# 2045.net
KiCad netlist of a schematic drawn in EAGLE
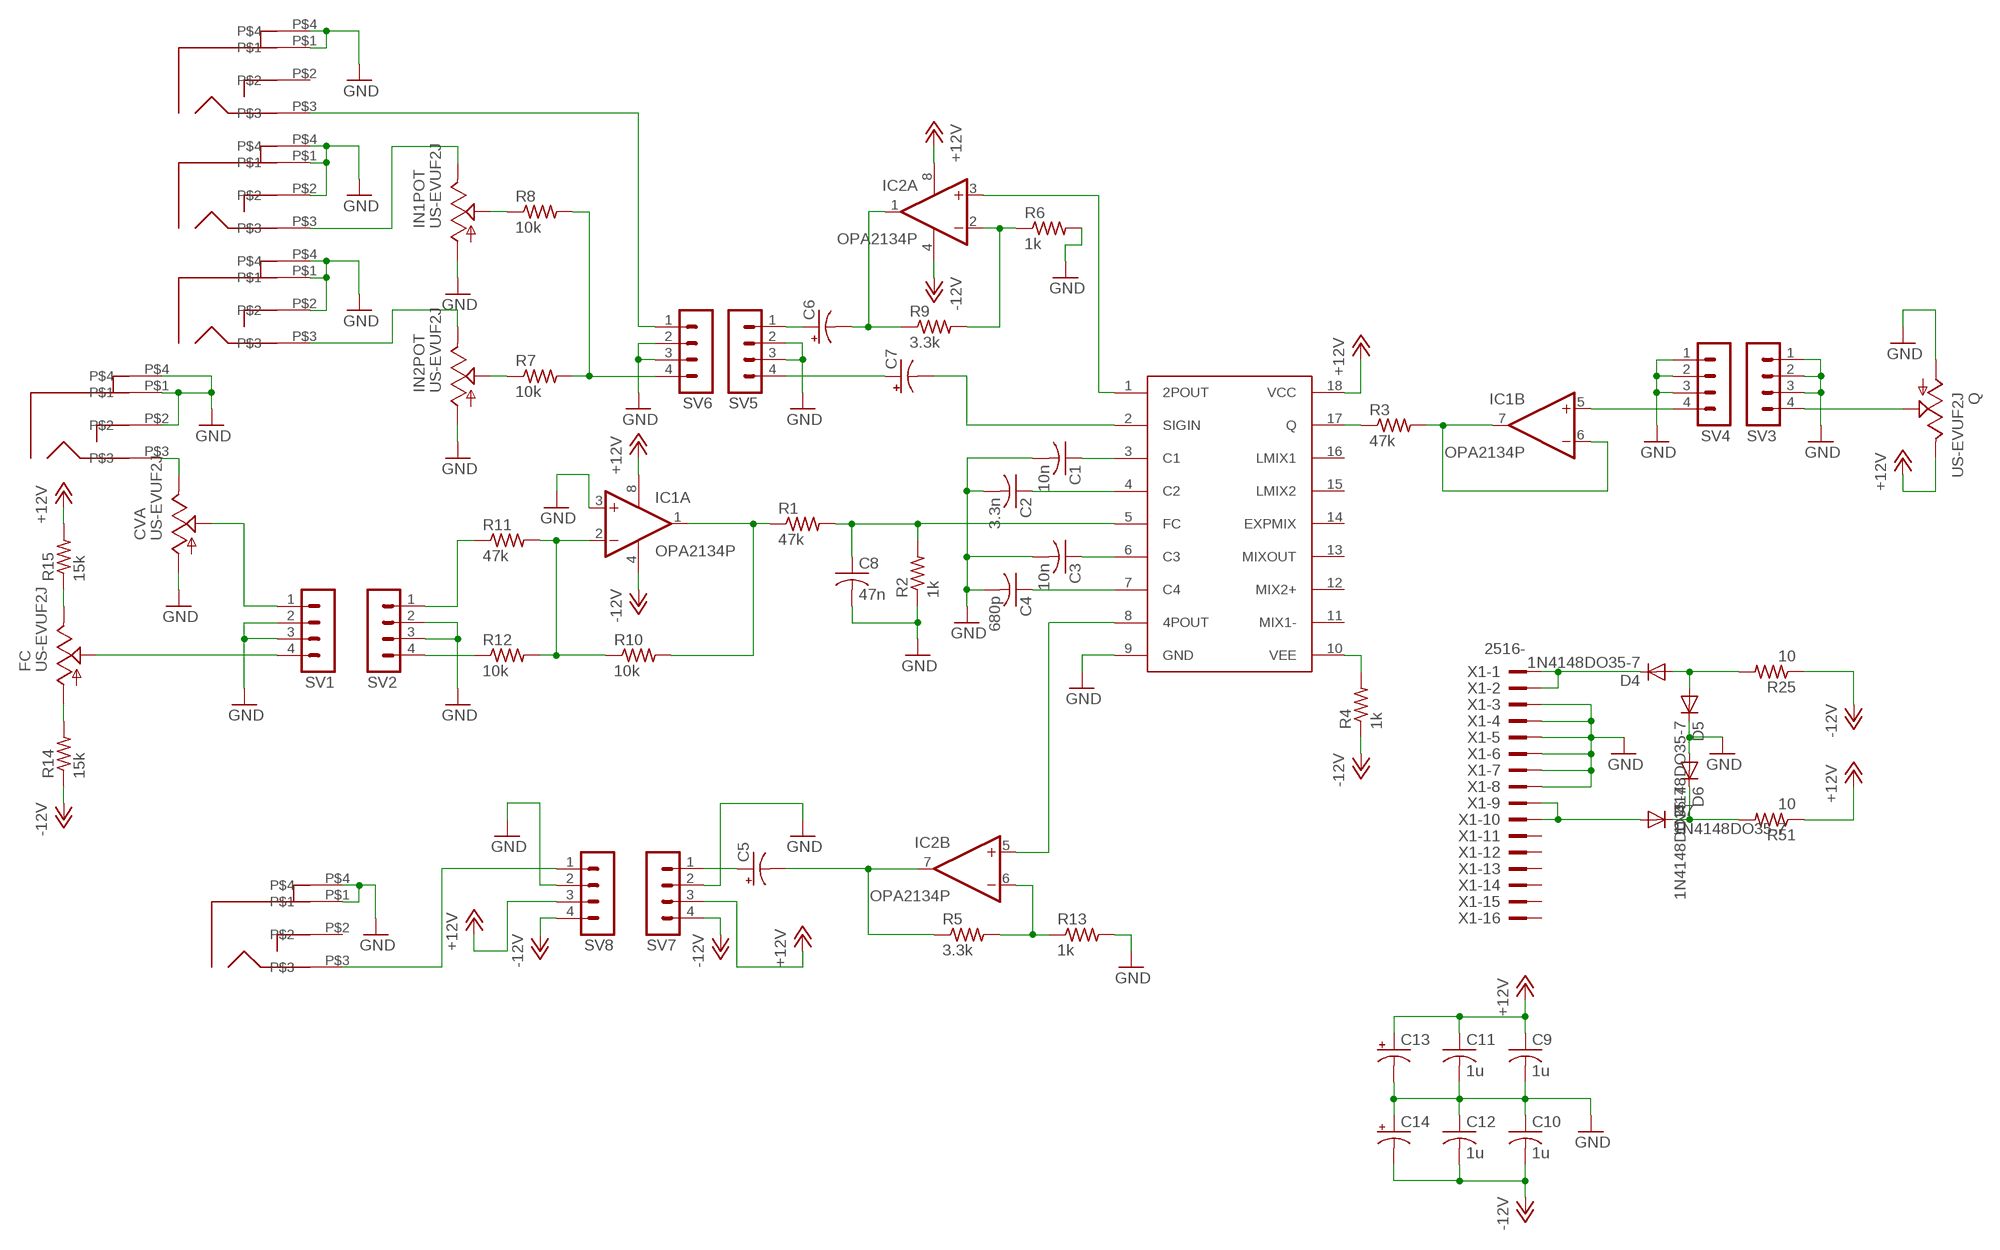
[diagram p0: schematic, sheet 1]

(export (version "E")
  (design (tool "Eeschema 10.0.6"))
  (components
    (comp (ref "2POUT")
      (value "PJ301BM")
      (footprint "eagle-import:PJ301BM")
      (libsource (lib "eagle-import") (part "PJ301BM"))
    )
    (comp (ref "4POUTPUT")
      (value "PJ301BM")
      (footprint "eagle-import:PJ301BM")
      (libsource (lib "eagle-import") (part "PJ301BM"))
    )
    (comp (ref "C1")
      (value "10n")
      (footprint "eagle-import:C050-025X075")
      (libsource (lib "eagle-import") (part "C-US050-025X075"))
    )
    (comp (ref "C2")
      (value "3.3n")
      (footprint "eagle-import:C050-025X075")
      (libsource (lib "eagle-import") (part "C-US050-025X075"))
    )
    (comp (ref "C3")
      (value "10n")
      (footprint "eagle-import:C050-025X075")
      (libsource (lib "eagle-import") (part "C-US050-025X075"))
    )
    (comp (ref "C4")
      (value "680p")
      (footprint "eagle-import:C050-025X075")
      (libsource (lib "eagle-import") (part "C-US050-025X075"))
    )
    (comp (ref "C5")
      (value "CPOL-USE2.5-7")
      (footprint "eagle-import:E2,5-7")
      (libsource (lib "eagle-import") (part "CPOL-USE2.5-7"))
    )
    (comp (ref "C6")
      (value "CPOL-USE2.5-7")
      (footprint "eagle-import:E2,5-7")
      (libsource (lib "eagle-import") (part "CPOL-USE2.5-7"))
    )
    (comp (ref "C7")
      (value "CPOL-USE2.5-7")
      (footprint "eagle-import:E2,5-7")
      (libsource (lib "eagle-import") (part "CPOL-USE2.5-7"))
    )
    (comp (ref "C8")
      (value "47n")
      (footprint "eagle-import:C050-025X075")
      (libsource (lib "eagle-import") (part "C-US050-025X075"))
    )
    (comp (ref "C9")
      (value "1u")
      (footprint "eagle-import:C050-025X075")
      (libsource (lib "eagle-import") (part "C-US050-025X075"))
    )
    (comp (ref "C10")
      (value "1u")
      (footprint "eagle-import:C050-025X075")
      (libsource (lib "eagle-import") (part "C-US050-025X075"))
    )
    (comp (ref "C11")
      (value "1u")
      (footprint "eagle-import:C050-025X075")
      (libsource (lib "eagle-import") (part "C-US050-025X075"))
    )
    (comp (ref "C12")
      (value "1u")
      (footprint "eagle-import:C050-025X075")
      (libsource (lib "eagle-import") (part "C-US050-025X075"))
    )
    (comp (ref "C13")
      (value "CPOL-USE2.5-7")
      (footprint "eagle-import:E2,5-7")
      (libsource (lib "eagle-import") (part "CPOL-USE2.5-7"))
    )
    (comp (ref "C14")
      (value "CPOL-USE2.5-7")
      (footprint "eagle-import:E2,5-7")
      (libsource (lib "eagle-import") (part "CPOL-USE2.5-7"))
    )
    (comp (ref "CVA")
      (value "US-EVUF2J")
      (footprint "eagle-import:EVUFXJ")
      (libsource (lib "eagle-import") (part "US-EVUF2J"))
    )
    (comp (ref "CVIN")
      (value "PJ301BM")
      (footprint "eagle-import:PJ301BM")
      (libsource (lib "eagle-import") (part "PJ301BM"))
    )
    (comp (ref "D4")
      (value "1N4148DO35-7")
      (footprint "eagle-import:DO35-7")
      (libsource (lib "eagle-import") (part "1N4148DO35-7"))
    )
    (comp (ref "D5")
      (value "1N4148DO35-7")
      (footprint "eagle-import:DO35-7")
      (libsource (lib "eagle-import") (part "1N4148DO35-7"))
    )
    (comp (ref "D6")
      (value "1N4148DO35-7")
      (footprint "eagle-import:DO35-7")
      (libsource (lib "eagle-import") (part "1N4148DO35-7"))
    )
    (comp (ref "D7")
      (value "1N4148DO35-7")
      (footprint "eagle-import:DO35-7")
      (libsource (lib "eagle-import") (part "1N4148DO35-7"))
    )
    (comp (ref "FC")
      (value "US-EVUF2J")
      (footprint "eagle-import:EVUFXJ")
      (libsource (lib "eagle-import") (part "US-EVUF2J"))
    )
    (comp (ref "IC1")
      (value "OPA2134P")
      (footprint "eagle-import:DIL08")
      (libsource (lib "eagle-import") (part "OPA2134P"))
    )
    (comp (ref "IC2")
      (value "OPA2134P")
      (footprint "eagle-import:DIL08")
      (libsource (lib "eagle-import") (part "OPA2134P"))
    )
    (comp (ref "IN")
      (value "PJ301BM")
      (footprint "eagle-import:PJ301BM")
      (libsource (lib "eagle-import") (part "PJ301BM"))
    )
    (comp (ref "IN1POT")
      (value "US-EVUF2J")
      (footprint "eagle-import:EVUFXJ")
      (libsource (lib "eagle-import") (part "US-EVUF2J"))
    )
    (comp (ref "IN2")
      (value "PJ301BM")
      (footprint "eagle-import:PJ301BM")
      (libsource (lib "eagle-import") (part "PJ301BM"))
    )
    (comp (ref "IN2POT")
      (value "US-EVUF2J")
      (footprint "eagle-import:EVUFXJ")
      (libsource (lib "eagle-import") (part "US-EVUF2J"))
    )
    (comp (ref "Q")
      (value "US-EVUF2J")
      (footprint "eagle-import:EVUFXJ")
      (libsource (lib "eagle-import") (part "US-EVUF2J"))
    )
    (comp (ref "R1")
      (value "47k")
      (footprint "eagle-import:0204_7")
      (libsource (lib "eagle-import") (part "R-US_0204/7"))
    )
    (comp (ref "R2")
      (value "1k")
      (footprint "eagle-import:0204_7")
      (libsource (lib "eagle-import") (part "R-US_0204/7"))
    )
    (comp (ref "R3")
      (value "47k")
      (footprint "eagle-import:0204_7")
      (libsource (lib "eagle-import") (part "R-US_0204/7"))
    )
    (comp (ref "R4")
      (value "1k")
      (footprint "eagle-import:0204_7")
      (libsource (lib "eagle-import") (part "R-US_0204/7"))
    )
    (comp (ref "R5")
      (value "3.3k")
      (footprint "eagle-import:0204_7")
      (libsource (lib "eagle-import") (part "R-US_0204/7"))
    )
    (comp (ref "R6")
      (value "1k")
      (footprint "eagle-import:0204_7")
      (libsource (lib "eagle-import") (part "R-US_0204/7"))
    )
    (comp (ref "R7")
      (value "10k")
      (footprint "eagle-import:0204_7")
      (libsource (lib "eagle-import") (part "R-US_0204/7"))
    )
    (comp (ref "R8")
      (value "10k")
      (footprint "eagle-import:0204_7")
      (libsource (lib "eagle-import") (part "R-US_0204/7"))
    )
    (comp (ref "R9")
      (value "3.3k")
      (footprint "eagle-import:0204_7")
      (libsource (lib "eagle-import") (part "R-US_0204/7"))
    )
    (comp (ref "R10")
      (value "10k")
      (footprint "eagle-import:0204_7")
      (libsource (lib "eagle-import") (part "R-US_0204/7"))
    )
    (comp (ref "R11")
      (value "47k")
      (footprint "eagle-import:0204_7")
      (libsource (lib "eagle-import") (part "R-US_0204/7"))
    )
    (comp (ref "R12")
      (value "10k")
      (footprint "eagle-import:0204_7")
      (libsource (lib "eagle-import") (part "R-US_0204/7"))
    )
    (comp (ref "R13")
      (value "1k")
      (footprint "eagle-import:0204_7")
      (libsource (lib "eagle-import") (part "R-US_0204/7"))
    )
    (comp (ref "R14")
      (value "15k")
      (footprint "eagle-import:0204_7")
      (libsource (lib "eagle-import") (part "R-US_0204/7"))
    )
    (comp (ref "R15")
      (value "15k")
      (footprint "eagle-import:0204_7")
      (libsource (lib "eagle-import") (part "R-US_0204/7"))
    )
    (comp (ref "R25")
      (value "10")
      (footprint "eagle-import:0207_2V")
      (libsource (lib "eagle-import") (part "R-US_0207/2V"))
    )
    (comp (ref "R51")
      (value "10")
      (footprint "eagle-import:0207_2V")
      (libsource (lib "eagle-import") (part "R-US_0207/2V"))
    )
    (comp (ref "SV1")
      (value "MA04-1")
      (footprint "eagle-import:MA04-1")
      (libsource (lib "eagle-import") (part "MA04-1"))
    )
    (comp (ref "SV2")
      (value "MA04-1")
      (footprint "eagle-import:MA04-1")
      (libsource (lib "eagle-import") (part "MA04-1"))
    )
    (comp (ref "SV3")
      (value "MA04-1")
      (footprint "eagle-import:MA04-1")
      (libsource (lib "eagle-import") (part "MA04-1"))
    )
    (comp (ref "SV4")
      (value "MA04-1")
      (footprint "eagle-import:MA04-1")
      (libsource (lib "eagle-import") (part "MA04-1"))
    )
    (comp (ref "SV5")
      (value "MA04-1")
      (footprint "eagle-import:MA04-1")
      (libsource (lib "eagle-import") (part "MA04-1"))
    )
    (comp (ref "SV6")
      (value "MA04-1")
      (footprint "eagle-import:MA04-1")
      (libsource (lib "eagle-import") (part "MA04-1"))
    )
    (comp (ref "SV7")
      (value "MA04-1")
      (footprint "eagle-import:MA04-1")
      (libsource (lib "eagle-import") (part "MA04-1"))
    )
    (comp (ref "SV8")
      (value "MA04-1")
      (footprint "eagle-import:MA04-1")
      (libsource (lib "eagle-import") (part "MA04-1"))
    )
    (comp (ref "U$1")
      (value "SSM2045")
      (footprint "eagle-import:DIL18")
      (libsource (lib "eagle-import") (part "SSM2045"))
    )
    (comp (ref "X1")
      (value "2516-")
      (footprint "eagle-import:PAK100_2500-16")
      (libsource (lib "eagle-import") (part "2516-"))
    )
  )
  (nets
    (net (code "1") (name "+12V") (class "Default")
      (node (ref "C11") (pin "1") (pinfunction "1_1") (pintype "passive"))
      (node (ref "C13") (pin "+") (pinfunction "+_+") (pintype "passive"))
      (node (ref "C9") (pin "1") (pinfunction "1_1") (pintype "passive"))
      (node (ref "IC1") (pin "8") (pinfunction "V+_8") (pintype "power_in"))
      (node (ref "IC2") (pin "8") (pinfunction "V+_8") (pintype "power_in"))
      (node (ref "Q") (pin "3") (pinfunction "E_3") (pintype "passive"))
      (node (ref "R15") (pin "2") (pinfunction "2_2") (pintype "passive"))
      (node (ref "R51") (pin "1") (pinfunction "1_1") (pintype "passive"))
      (node (ref "SV7") (pin "3") (pinfunction "3_3") (pintype "passive"))
      (node (ref "SV8") (pin "3") (pinfunction "3_3") (pintype "passive"))
      (node (ref "U$1") (pin "18") (pinfunction "VCC_18") (pintype "bidirectional"))
    )
    (net (code "2") (name "-12V") (class "Default")
      (node (ref "C10") (pin "2") (pinfunction "2_2") (pintype "passive"))
      (node (ref "C12") (pin "2") (pinfunction "2_2") (pintype "passive"))
      (node (ref "C14") (pin "-") (pinfunction "-_-") (pintype "passive"))
      (node (ref "IC1") (pin "4") (pinfunction "V-_4") (pintype "power_in"))
      (node (ref "IC2") (pin "4") (pinfunction "V-_4") (pintype "power_in"))
      (node (ref "R14") (pin "1") (pinfunction "1_1") (pintype "passive"))
      (node (ref "R25") (pin "1") (pinfunction "1_1") (pintype "passive"))
      (node (ref "R4") (pin "1") (pinfunction "1_1") (pintype "passive"))
      (node (ref "SV7") (pin "4") (pinfunction "4_4") (pintype "passive"))
      (node (ref "SV8") (pin "4") (pinfunction "4_4") (pintype "passive"))
    )
    (net (code "3") (name "GND") (class "Default")
      (node (ref "2POUT") (pin "P$1") (pinfunction "P$1_P$1") (pintype "bidirectional"))
      (node (ref "2POUT") (pin "P$4") (pinfunction "P$4_P$4") (pintype "bidirectional"))
      (node (ref "4POUTPUT") (pin "P$1") (pinfunction "P$1_P$1") (pintype "bidirectional"))
      (node (ref "4POUTPUT") (pin "P$4") (pinfunction "P$4_P$4") (pintype "bidirectional"))
      (node (ref "C1") (pin "2") (pinfunction "2_2") (pintype "passive"))
      (node (ref "C10") (pin "1") (pinfunction "1_1") (pintype "passive"))
      (node (ref "C11") (pin "2") (pinfunction "2_2") (pintype "passive"))
      (node (ref "C12") (pin "1") (pinfunction "1_1") (pintype "passive"))
      (node (ref "C13") (pin "-") (pinfunction "-_-") (pintype "passive"))
      (node (ref "C14") (pin "+") (pinfunction "+_+") (pintype "passive"))
      (node (ref "C2") (pin "2") (pinfunction "2_2") (pintype "passive"))
      (node (ref "C3") (pin "2") (pinfunction "2_2") (pintype "passive"))
      (node (ref "C4") (pin "2") (pinfunction "2_2") (pintype "passive"))
      (node (ref "C8") (pin "2") (pinfunction "2_2") (pintype "passive"))
      (node (ref "C9") (pin "2") (pinfunction "2_2") (pintype "passive"))
      (node (ref "CVA") (pin "1") (pinfunction "A_1") (pintype "passive"))
      (node (ref "CVIN") (pin "P$1") (pinfunction "P$1_P$1") (pintype "bidirectional"))
      (node (ref "CVIN") (pin "P$2") (pinfunction "P$2_P$2") (pintype "bidirectional"))
      (node (ref "CVIN") (pin "P$4") (pinfunction "P$4_P$4") (pintype "bidirectional"))
      (node (ref "D5") (pin "C") (pinfunction "C_C") (pintype "passive"))
      (node (ref "D6") (pin "A") (pinfunction "A_A") (pintype "passive"))
      (node (ref "IC1") (pin "3") (pinfunction "+IN_3") (pintype "input"))
      (node (ref "IN") (pin "P$1") (pinfunction "P$1_P$1") (pintype "bidirectional"))
      (node (ref "IN") (pin "P$2") (pinfunction "P$2_P$2") (pintype "bidirectional"))
      (node (ref "IN") (pin "P$4") (pinfunction "P$4_P$4") (pintype "bidirectional"))
      (node (ref "IN1POT") (pin "1") (pinfunction "A_1") (pintype "passive"))
      (node (ref "IN2") (pin "P$1") (pinfunction "P$1_P$1") (pintype "bidirectional"))
      (node (ref "IN2") (pin "P$2") (pinfunction "P$2_P$2") (pintype "bidirectional"))
      (node (ref "IN2") (pin "P$4") (pinfunction "P$4_P$4") (pintype "bidirectional"))
      (node (ref "IN2POT") (pin "1") (pinfunction "A_1") (pintype "passive"))
      (node (ref "Q") (pin "1") (pinfunction "A_1") (pintype "passive"))
      (node (ref "R13") (pin "2") (pinfunction "2_2") (pintype "passive"))
      (node (ref "R2") (pin "1") (pinfunction "1_1") (pintype "passive"))
      (node (ref "R6") (pin "2") (pinfunction "2_2") (pintype "passive"))
      (node (ref "SV1") (pin "2") (pinfunction "2_2") (pintype "passive"))
      (node (ref "SV1") (pin "3") (pinfunction "3_3") (pintype "passive"))
      (node (ref "SV2") (pin "2") (pinfunction "2_2") (pintype "passive"))
      (node (ref "SV2") (pin "3") (pinfunction "3_3") (pintype "passive"))
      (node (ref "SV3") (pin "1") (pinfunction "1_1") (pintype "passive"))
      (node (ref "SV3") (pin "2") (pinfunction "2_2") (pintype "passive"))
      (node (ref "SV3") (pin "3") (pinfunction "3_3") (pintype "passive"))
      (node (ref "SV4") (pin "1") (pinfunction "1_1") (pintype "passive"))
      (node (ref "SV4") (pin "2") (pinfunction "2_2") (pintype "passive"))
      (node (ref "SV4") (pin "3") (pinfunction "3_3") (pintype "passive"))
      (node (ref "SV5") (pin "2") (pinfunction "2_2") (pintype "passive"))
      (node (ref "SV5") (pin "3") (pinfunction "3_3") (pintype "passive"))
      (node (ref "SV6") (pin "2") (pinfunction "2_2") (pintype "passive"))
      (node (ref "SV6") (pin "3") (pinfunction "3_3") (pintype "passive"))
      (node (ref "SV7") (pin "2") (pinfunction "2_2") (pintype "passive"))
      (node (ref "SV8") (pin "2") (pinfunction "2_2") (pintype "passive"))
      (node (ref "U$1") (pin "9") (pinfunction "GND_9") (pintype "bidirectional"))
      (node (ref "X1") (pin "3") (pinfunction "KL_3") (pintype "passive"))
      (node (ref "X1") (pin "4") (pinfunction "KL_4") (pintype "passive"))
      (node (ref "X1") (pin "5") (pinfunction "KL_5") (pintype "passive"))
      (node (ref "X1") (pin "6") (pinfunction "KL_6") (pintype "passive"))
      (node (ref "X1") (pin "7") (pinfunction "KL_7") (pintype "passive"))
      (node (ref "X1") (pin "8") (pinfunction "KL_8") (pintype "passive"))
    )
    (net (code "4") (name "Net-(2POUT-PadP$3)") (class "Default")
      (node (ref "2POUT") (pin "P$3") (pinfunction "P$3_P$3") (pintype "bidirectional"))
      (node (ref "SV6") (pin "1") (pinfunction "1_1") (pintype "passive"))
    )
    (net (code "5") (name "Net-(4POUTPUT-PadP$3)") (class "Default")
      (node (ref "4POUTPUT") (pin "P$3") (pinfunction "P$3_P$3") (pintype "bidirectional"))
      (node (ref "SV8") (pin "1") (pinfunction "1_1") (pintype "passive"))
    )
    (net (code "6") (name "Net-(C5-Pad+)") (class "Default")
      (node (ref "C5") (pin "+") (pinfunction "+_+") (pintype "passive"))
      (node (ref "SV7") (pin "1") (pinfunction "1_1") (pintype "passive"))
    )
    (net (code "7") (name "Net-(C6-Pad+)") (class "Default")
      (node (ref "C6") (pin "+") (pinfunction "+_+") (pintype "passive"))
      (node (ref "SV5") (pin "1") (pinfunction "1_1") (pintype "passive"))
    )
    (net (code "8") (name "Net-(C7-Pad+)") (class "Default")
      (node (ref "C7") (pin "+") (pinfunction "+_+") (pintype "passive"))
      (node (ref "SV5") (pin "4") (pinfunction "4_4") (pintype "passive"))
    )
    (net (code "9") (name "Net-(CVA-E)") (class "Default")
      (node (ref "CVA") (pin "3") (pinfunction "E_3") (pintype "passive"))
      (node (ref "CVIN") (pin "P$3") (pinfunction "P$3_P$3") (pintype "bidirectional"))
    )
    (net (code "10") (name "Net-(CVA-S)") (class "Default")
      (node (ref "CVA") (pin "2") (pinfunction "S_2") (pintype "passive"))
      (node (ref "SV1") (pin "1") (pinfunction "1_1") (pintype "passive"))
    )
    (net (code "11") (name "Net-(D4-PadA)") (class "Default")
      (node (ref "D4") (pin "A") (pinfunction "A_A") (pintype "passive"))
      (node (ref "D5") (pin "A") (pinfunction "A_A") (pintype "passive"))
      (node (ref "R25") (pin "2") (pinfunction "2_2") (pintype "passive"))
    )
    (net (code "12") (name "Net-(D6-PadC)") (class "Default")
      (node (ref "D6") (pin "C") (pinfunction "C_C") (pintype "passive"))
      (node (ref "D7") (pin "C") (pinfunction "C_C") (pintype "passive"))
      (node (ref "R51") (pin "2") (pinfunction "2_2") (pintype "passive"))
    )
    (net (code "13") (name "Net-(FC-A)") (class "Default")
      (node (ref "FC") (pin "1") (pinfunction "A_1") (pintype "passive"))
      (node (ref "R14") (pin "2") (pinfunction "2_2") (pintype "passive"))
    )
    (net (code "14") (name "Net-(FC-E)") (class "Default")
      (node (ref "FC") (pin "3") (pinfunction "E_3") (pintype "passive"))
      (node (ref "R15") (pin "1") (pinfunction "1_1") (pintype "passive"))
    )
    (net (code "15") (name "Net-(FC-S)") (class "Default")
      (node (ref "FC") (pin "2") (pinfunction "S_2") (pintype "passive"))
      (node (ref "SV1") (pin "4") (pinfunction "4_4") (pintype "passive"))
    )
    (net (code "16") (name "Net-(IC1A--IN)") (class "Default")
      (node (ref "IC1") (pin "2") (pinfunction "-IN_2") (pintype "input"))
      (node (ref "R10") (pin "1") (pinfunction "1_1") (pintype "passive"))
      (node (ref "R11") (pin "2") (pinfunction "2_2") (pintype "passive"))
      (node (ref "R12") (pin "2") (pinfunction "2_2") (pintype "passive"))
    )
    (net (code "17") (name "Net-(IC1A-OUT)") (class "Default")
      (node (ref "IC1") (pin "1") (pinfunction "OUT_1") (pintype "output"))
      (node (ref "R1") (pin "1") (pinfunction "1_1") (pintype "passive"))
      (node (ref "R10") (pin "2") (pinfunction "2_2") (pintype "passive"))
    )
    (net (code "18") (name "Net-(IC1B-+IN)") (class "Default")
      (node (ref "IC1") (pin "5") (pinfunction "+IN_5") (pintype "input"))
      (node (ref "SV4") (pin "4") (pinfunction "4_4") (pintype "passive"))
    )
    (net (code "19") (name "Net-(IC1B--IN)") (class "Default")
      (node (ref "IC1") (pin "6") (pinfunction "-IN_6") (pintype "input"))
      (node (ref "IC1") (pin "7") (pinfunction "OUT_7") (pintype "output"))
      (node (ref "R3") (pin "2") (pinfunction "2_2") (pintype "passive"))
    )
    (net (code "20") (name "Net-(IC2A-+IN)") (class "Default")
      (node (ref "IC2") (pin "3") (pinfunction "+IN_3") (pintype "input"))
      (node (ref "U$1") (pin "1") (pinfunction "2POUT_1") (pintype "bidirectional"))
    )
    (net (code "21") (name "Net-(IC2A--IN)") (class "Default")
      (node (ref "IC2") (pin "2") (pinfunction "-IN_2") (pintype "input"))
      (node (ref "R6") (pin "1") (pinfunction "1_1") (pintype "passive"))
      (node (ref "R9") (pin "2") (pinfunction "2_2") (pintype "passive"))
    )
    (net (code "22") (name "Net-(IC2A-OUT)") (class "Default")
      (node (ref "C6") (pin "-") (pinfunction "-_-") (pintype "passive"))
      (node (ref "IC2") (pin "1") (pinfunction "OUT_1") (pintype "output"))
      (node (ref "R9") (pin "1") (pinfunction "1_1") (pintype "passive"))
    )
    (net (code "23") (name "Net-(IC2B-+IN)") (class "Default")
      (node (ref "IC2") (pin "5") (pinfunction "+IN_5") (pintype "input"))
      (node (ref "U$1") (pin "8") (pinfunction "4POUT_8") (pintype "bidirectional"))
    )
    (net (code "24") (name "Net-(IC2B--IN)") (class "Default")
      (node (ref "IC2") (pin "6") (pinfunction "-IN_6") (pintype "input"))
      (node (ref "R13") (pin "1") (pinfunction "1_1") (pintype "passive"))
      (node (ref "R5") (pin "2") (pinfunction "2_2") (pintype "passive"))
    )
    (net (code "25") (name "Net-(IC2B-OUT)") (class "Default")
      (node (ref "C5") (pin "-") (pinfunction "-_-") (pintype "passive"))
      (node (ref "IC2") (pin "7") (pinfunction "OUT_7") (pintype "output"))
      (node (ref "R5") (pin "1") (pinfunction "1_1") (pintype "passive"))
    )
    (net (code "26") (name "Net-(IN1POT-E)") (class "Default")
      (node (ref "IN") (pin "P$3") (pinfunction "P$3_P$3") (pintype "bidirectional"))
      (node (ref "IN1POT") (pin "3") (pinfunction "E_3") (pintype "passive"))
    )
    (net (code "27") (name "Net-(IN1POT-S)") (class "Default")
      (node (ref "IN1POT") (pin "2") (pinfunction "S_2") (pintype "passive"))
      (node (ref "R8") (pin "1") (pinfunction "1_1") (pintype "passive"))
    )
    (net (code "28") (name "Net-(IN2POT-E)") (class "Default")
      (node (ref "IN2") (pin "P$3") (pinfunction "P$3_P$3") (pintype "bidirectional"))
      (node (ref "IN2POT") (pin "3") (pinfunction "E_3") (pintype "passive"))
    )
    (net (code "29") (name "Net-(IN2POT-S)") (class "Default")
      (node (ref "IN2POT") (pin "2") (pinfunction "S_2") (pintype "passive"))
      (node (ref "R7") (pin "1") (pinfunction "1_1") (pintype "passive"))
    )
    (net (code "30") (name "Net-(Q-S)") (class "Default")
      (node (ref "Q") (pin "2") (pinfunction "S_2") (pintype "passive"))
      (node (ref "SV3") (pin "4") (pinfunction "4_4") (pintype "passive"))
    )
    (net (code "31") (name "Net-(R7-Pad2)") (class "Default")
      (node (ref "R7") (pin "2") (pinfunction "2_2") (pintype "passive"))
      (node (ref "R8") (pin "2") (pinfunction "2_2") (pintype "passive"))
      (node (ref "SV6") (pin "4") (pinfunction "4_4") (pintype "passive"))
    )
    (net (code "32") (name "Net-(R11-Pad1)") (class "Default")
      (node (ref "R11") (pin "1") (pinfunction "1_1") (pintype "passive"))
      (node (ref "SV2") (pin "1") (pinfunction "1_1") (pintype "passive"))
    )
    (net (code "33") (name "Net-(R12-Pad1)") (class "Default")
      (node (ref "R12") (pin "1") (pinfunction "1_1") (pintype "passive"))
      (node (ref "SV2") (pin "4") (pinfunction "4_4") (pintype "passive"))
    )
    (net (code "34") (name "Net-(U$1-C1)") (class "Default")
      (node (ref "C1") (pin "1") (pinfunction "1_1") (pintype "passive"))
      (node (ref "U$1") (pin "3") (pinfunction "C1_3") (pintype "bidirectional"))
    )
    (net (code "35") (name "Net-(U$1-C2)") (class "Default")
      (node (ref "C2") (pin "1") (pinfunction "1_1") (pintype "passive"))
      (node (ref "U$1") (pin "4") (pinfunction "C2_4") (pintype "bidirectional"))
    )
    (net (code "36") (name "Net-(U$1-C3)") (class "Default")
      (node (ref "C3") (pin "1") (pinfunction "1_1") (pintype "passive"))
      (node (ref "U$1") (pin "6") (pinfunction "C3_6") (pintype "bidirectional"))
    )
    (net (code "37") (name "Net-(U$1-C4)") (class "Default")
      (node (ref "C4") (pin "1") (pinfunction "1_1") (pintype "passive"))
      (node (ref "U$1") (pin "7") (pinfunction "C4_7") (pintype "bidirectional"))
    )
    (net (code "38") (name "Net-(U$1-FC)") (class "Default")
      (node (ref "C8") (pin "1") (pinfunction "1_1") (pintype "passive"))
      (node (ref "R1") (pin "2") (pinfunction "2_2") (pintype "passive"))
      (node (ref "R2") (pin "2") (pinfunction "2_2") (pintype "passive"))
      (node (ref "U$1") (pin "5") (pinfunction "FC_5") (pintype "bidirectional"))
    )
    (net (code "39") (name "Net-(U$1-Q)") (class "Default")
      (node (ref "R3") (pin "1") (pinfunction "1_1") (pintype "passive"))
      (node (ref "U$1") (pin "17") (pinfunction "Q_17") (pintype "bidirectional"))
    )
    (net (code "40") (name "Net-(U$1-SIGIN)") (class "Default")
      (node (ref "C7") (pin "-") (pinfunction "-_-") (pintype "passive"))
      (node (ref "U$1") (pin "2") (pinfunction "SIGIN_2") (pintype "bidirectional"))
    )
    (net (code "41") (name "Net-(U$1-VEE)") (class "Default")
      (node (ref "R4") (pin "2") (pinfunction "2_2") (pintype "passive"))
      (node (ref "U$1") (pin "10") (pinfunction "VEE_10") (pintype "bidirectional"))
    )
    (net (code "42") (name "Net-(X1A-KL)") (class "Default")
      (node (ref "D4") (pin "C") (pinfunction "C_C") (pintype "passive"))
      (node (ref "X1") (pin "1") (pinfunction "KL_1") (pintype "passive"))
      (node (ref "X1") (pin "2") (pinfunction "KL_2") (pintype "passive"))
    )
    (net (code "43") (name "Net-(X1B-KL)") (class "Default")
      (node (ref "D7") (pin "A") (pinfunction "A_A") (pintype "passive"))
      (node (ref "X1") (pin "10") (pinfunction "KL_10") (pintype "passive"))
      (node (ref "X1") (pin "9") (pinfunction "KL_9") (pintype "passive"))
    )
    (net (code "44") (name "unconnected-(2POUT-PadP$2)") (class "Default")
      (node (ref "2POUT") (pin "P$2") (pinfunction "P$2_P$2") (pintype "bidirectional"))
    )
    (net (code "45") (name "unconnected-(4POUTPUT-PadP$2)") (class "Default")
      (node (ref "4POUTPUT") (pin "P$2") (pinfunction "P$2_P$2") (pintype "bidirectional"))
    )
    (net (code "46") (name "unconnected-(U$1-EXPMIX-Pad14)") (class "Default")
      (node (ref "U$1") (pin "14") (pinfunction "EXPMIX_14") (pintype "bidirectional"))
    )
    (net (code "47") (name "unconnected-(U$1-LMIX1-Pad16)") (class "Default")
      (node (ref "U$1") (pin "16") (pinfunction "LMIX1_16") (pintype "bidirectional"))
    )
    (net (code "48") (name "unconnected-(U$1-LMIX2-Pad15)") (class "Default")
      (node (ref "U$1") (pin "15") (pinfunction "LMIX2_15") (pintype "bidirectional"))
    )
    (net (code "49") (name "unconnected-(U$1-MIX1--Pad11)") (class "Default")
      (node (ref "U$1") (pin "11") (pinfunction "MIX1-_11") (pintype "bidirectional"))
    )
    (net (code "50") (name "unconnected-(U$1-MIX2+-Pad12)") (class "Default")
      (node (ref "U$1") (pin "12") (pinfunction "MIX2+_12") (pintype "bidirectional"))
    )
    (net (code "51") (name "unconnected-(U$1-MIXOUT-Pad13)") (class "Default")
      (node (ref "U$1") (pin "13") (pinfunction "MIXOUT_13") (pintype "bidirectional"))
    )
    (net (code "52") (name "unconnected-(X1C-KL-Pad11)") (class "Default")
      (node (ref "X1") (pin "11") (pinfunction "KL_11") (pintype "passive"))
    )
    (net (code "53") (name "unconnected-(X1D-KL-Pad12)") (class "Default")
      (node (ref "X1") (pin "12") (pinfunction "KL_12") (pintype "passive"))
    )
    (net (code "54") (name "unconnected-(X1E-KL-Pad13)") (class "Default")
      (node (ref "X1") (pin "13") (pinfunction "KL_13") (pintype "passive"))
    )
    (net (code "55") (name "unconnected-(X1F-KL-Pad14)") (class "Default")
      (node (ref "X1") (pin "14") (pinfunction "KL_14") (pintype "passive"))
    )
    (net (code "56") (name "unconnected-(X1G-KL-Pad15)") (class "Default")
      (node (ref "X1") (pin "15") (pinfunction "KL_15") (pintype "passive"))
    )
    (net (code "57") (name "unconnected-(X1H-KL-Pad16)") (class "Default")
      (node (ref "X1") (pin "16") (pinfunction "KL_16") (pintype "passive"))
    )
  )
)
